# Inverter.net
KiCad netlist of a schematic drawn in Altium Designer
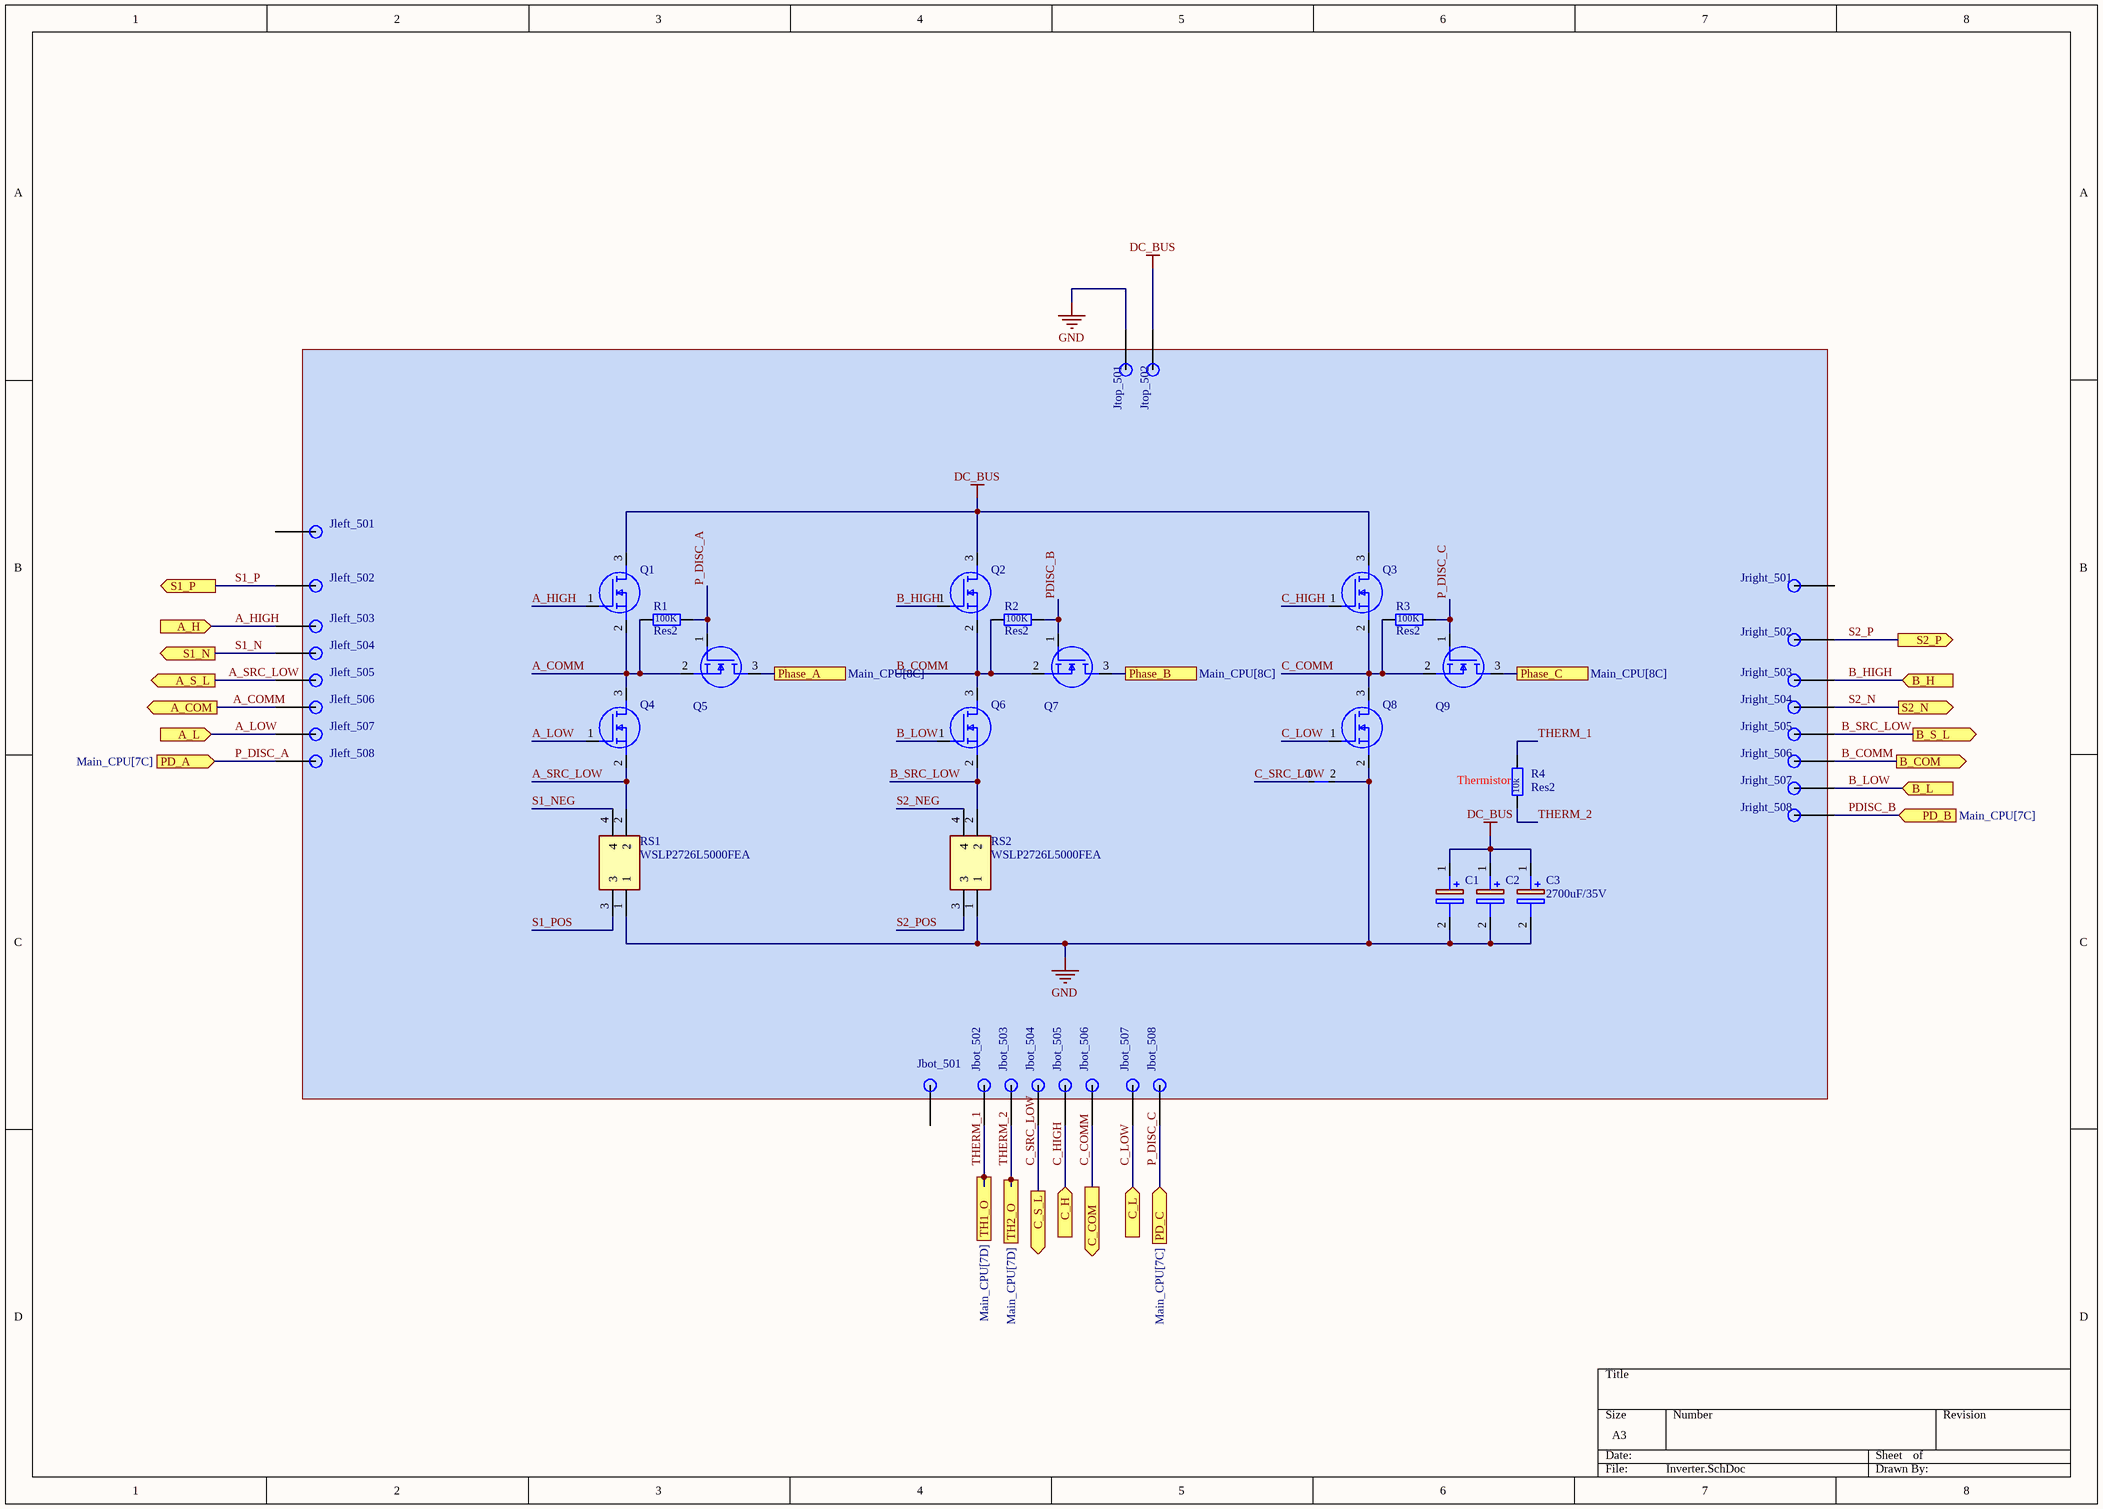
[diagram p0: Inverter.SchDoc]

(export (version "E")
  (design (tool "Eeschema 10.0.6"))
  (components
    (comp (ref "C1")
      (value "2700uF/35V")
      (footprint "SamacSys:CAPPM6032X280N")
      (description "Capacitor Polarised")
      (fields
        (field (name "MANUFACTURER_PART_NUMBER") "293D106X9025C2TE3")
        (field (name "MOUSER PART NUMBER") "74-293D106X9025C2TE3")
      )
      (libsource (lib "SamacSys") (part "293D106X9025C2TE3"))
    )
    (comp (ref "C2")
      (value "2700uF/35V")
      (footprint "SamacSys:CAPPM6032X280N")
      (description "Capacitor Polarised")
      (fields
        (field (name "MANUFACTURER_PART_NUMBER") "293D106X9025C2TE3")
        (field (name "MOUSER PART NUMBER") "74-293D106X9025C2TE3")
      )
      (libsource (lib "SamacSys") (part "293D106X9025C2TE3"))
    )
    (comp (ref "C3")
      (value "2700uF/35V")
      (footprint "SamacSys:CAPPM6032X280N")
      (description "Capacitor Polarised")
      (fields
        (field (name "MANUFACTURER_PART_NUMBER") "293D106X9025C2TE3")
        (field (name "MOUSER PART NUMBER") "74-293D106X9025C2TE3")
      )
      (libsource (lib "SamacSys") (part "293D106X9025C2TE3"))
    )
    (comp (ref "Jbot_501")
      (value "Pin_1mm")
      (footprint "Pin_1.5mm")
      (description "Pin_Connector")
      (fields (field (name "MPN") "X5511FV-02-C70D30-1000"))
      (libsource (lib "SamacSys") (part "Pin_1mm"))
    )
    (comp (ref "Jbot_502")
      (value "Pin_1mm")
      (footprint "Pin_1mm")
      (description "Pin_Connector")
      (fields (field (name "MPN") "X5511FV-02-C70D30-1000"))
      (libsource (lib "SamacSys") (part "Pin_1mm"))
    )
    (comp (ref "Jbot_503")
      (value "Pin_1mm")
      (footprint "Pin_1mm")
      (description "Pin_Connector")
      (fields (field (name "MPN") "X5511FV-02-C70D30-1000"))
      (libsource (lib "SamacSys") (part "Pin_1mm"))
    )
    (comp (ref "Jbot_504")
      (value "Pin_1mm")
      (footprint "Pin_1mm")
      (description "Pin_Connector")
      (fields (field (name "MPN") "X5511FV-02-C70D30-1000"))
      (libsource (lib "SamacSys") (part "Pin_1mm"))
    )
    (comp (ref "Jbot_505")
      (value "Pin_1mm")
      (footprint "Pin_1mm")
      (description "Pin_Connector")
      (fields (field (name "MPN") "X5511FV-02-C70D30-1000"))
      (libsource (lib "SamacSys") (part "Pin_1mm"))
    )
    (comp (ref "Jbot_506")
      (value "Pin_1mm")
      (footprint "Pin_1mm")
      (description "Pin_Connector")
      (fields (field (name "MPN") "X5511FV-02-C70D30-1000"))
      (libsource (lib "SamacSys") (part "Pin_1mm"))
    )
    (comp (ref "Jbot_507")
      (value "Pin_1mm")
      (footprint "Pin_1mm")
      (description "Pin_Connector")
      (fields (field (name "MPN") "X5511FV-02-C70D30-1000"))
      (libsource (lib "SamacSys") (part "Pin_1mm"))
    )
    (comp (ref "Jbot_508")
      (value "Pin_1mm")
      (footprint "Pin_1mm")
      (description "Pin_Connector")
      (fields (field (name "MPN") "X5511FV-02-C70D30-1000"))
      (libsource (lib "SamacSys") (part "Pin_1mm"))
    )
    (comp (ref "Jleft_501")
      (value "Pin_1mm")
      (footprint "Pin_1.5mm")
      (description "Pin_Connector")
      (fields (field (name "MPN") "X5511FV-02-C70D30-1000"))
      (libsource (lib "SamacSys") (part "Pin_1mm"))
    )
    (comp (ref "Jleft_502")
      (value "Pin_1mm")
      (footprint "Pin_1mm")
      (description "Pin_Connector")
      (fields (field (name "MPN") "X5511FV-02-C70D30-1000"))
      (libsource (lib "SamacSys") (part "Pin_1mm"))
    )
    (comp (ref "Jleft_503")
      (value "Pin_1mm")
      (footprint "Pin_1mm")
      (description "Pin_Connector")
      (fields (field (name "MPN") "X5511FV-02-C70D30-1000"))
      (libsource (lib "SamacSys") (part "Pin_1mm"))
    )
    (comp (ref "Jleft_504")
      (value "Pin_1mm")
      (footprint "Pin_1mm")
      (description "Pin_Connector")
      (fields (field (name "MPN") "X5511FV-02-C70D30-1000"))
      (libsource (lib "SamacSys") (part "Pin_1mm"))
    )
    (comp (ref "Jleft_505")
      (value "Pin_1mm")
      (footprint "Pin_1mm")
      (description "Pin_Connector")
      (fields (field (name "MPN") "X5511FV-02-C70D30-1000"))
      (libsource (lib "SamacSys") (part "Pin_1mm"))
    )
    (comp (ref "Jleft_506")
      (value "Pin_1mm")
      (footprint "Pin_1mm")
      (description "Pin_Connector")
      (fields (field (name "MPN") "X5511FV-02-C70D30-1000"))
      (libsource (lib "SamacSys") (part "Pin_1mm"))
    )
    (comp (ref "Jleft_507")
      (value "Pin_1mm")
      (footprint "Pin_1mm")
      (description "Pin_Connector")
      (fields (field (name "MPN") "X5511FV-02-C70D30-1000"))
      (libsource (lib "SamacSys") (part "Pin_1mm"))
    )
    (comp (ref "Jleft_508")
      (value "Pin_1mm")
      (footprint "Pin_1mm")
      (description "Pin_Connector")
      (fields (field (name "MPN") "X5511FV-02-C70D30-1000"))
      (libsource (lib "SamacSys") (part "Pin_1mm"))
    )
    (comp (ref "Jright_501")
      (value "Pin_1mm")
      (footprint "Pin_1.5mm")
      (description "Pin_Connector")
      (fields (field (name "MPN") "X5511FV-02-C70D30-1000"))
      (libsource (lib "SamacSys") (part "Pin_1mm"))
    )
    (comp (ref "Jright_502")
      (value "Pin_1mm")
      (footprint "Pin_1mm")
      (description "Pin_Connector")
      (fields (field (name "MPN") "X5511FV-02-C70D30-1000"))
      (libsource (lib "SamacSys") (part "Pin_1mm"))
    )
    (comp (ref "Jright_503")
      (value "Pin_1mm")
      (footprint "Pin_1mm")
      (description "Pin_Connector")
      (fields (field (name "MPN") "X5511FV-02-C70D30-1000"))
      (libsource (lib "SamacSys") (part "Pin_1mm"))
    )
    (comp (ref "Jright_504")
      (value "Pin_1mm")
      (footprint "Pin_1mm")
      (description "Pin_Connector")
      (fields (field (name "MPN") "X5511FV-02-C70D30-1000"))
      (libsource (lib "SamacSys") (part "Pin_1mm"))
    )
    (comp (ref "Jright_505")
      (value "Pin_1mm")
      (footprint "Pin_1mm")
      (description "Pin_Connector")
      (fields (field (name "MPN") "X5511FV-02-C70D30-1000"))
      (libsource (lib "SamacSys") (part "Pin_1mm"))
    )
    (comp (ref "Jright_506")
      (value "Pin_1mm")
      (footprint "Pin_1mm")
      (description "Pin_Connector")
      (fields (field (name "MPN") "X5511FV-02-C70D30-1000"))
      (libsource (lib "SamacSys") (part "Pin_1mm"))
    )
    (comp (ref "Jright_507")
      (value "Pin_1mm")
      (footprint "Pin_1mm")
      (description "Pin_Connector")
      (fields (field (name "MPN") "X5511FV-02-C70D30-1000"))
      (libsource (lib "SamacSys") (part "Pin_1mm"))
    )
    (comp (ref "Jright_508")
      (value "Pin_1mm")
      (footprint "Pin_1mm")
      (description "Pin_Connector")
      (fields (field (name "MPN") "X5511FV-02-C70D30-1000"))
      (libsource (lib "SamacSys") (part "Pin_1mm"))
    )
    (comp (ref "Jtop_501")
      (value "Pin_1mm")
      (footprint "Pin_1mm")
      (description "Pin_Connector")
      (fields (field (name "MPN") "X5511FV-02-C70D30-1000"))
      (libsource (lib "SamacSys") (part "Pin_1mm"))
    )
    (comp (ref "Jtop_502")
      (value "Pin_1mm")
      (footprint "Pin_1mm")
      (description "Pin_Connector")
      (fields (field (name "MPN") "X5511FV-02-C70D30-1000"))
      (libsource (lib "SamacSys") (part "Pin_1mm"))
    )
    (comp (ref "NT501")
      (value "Net_Tie")
      (footprint "Net_Tie_SMD")
      (description "Net Tie")
      (libsource (lib "SamacSys") (part "Net_Tie"))
    )
    (comp (ref "Q1")
      (value "IPT010N08NM5ATMA1")
      (footprint "SamacSys:IPT010N08NM5ATMA1")
      (description "MOSFET (N-Channel)")
      (fields (field (name "MOUSER PART NUMBER") "726-IPT010N08NM5ATM1"))
      (libsource (lib "SamacSys") (part "IPT010N08NM5ATMA1"))
    )
    (comp (ref "Q2")
      (value "IPT010N08NM5ATMA1")
      (footprint "SamacSys:IPT010N08NM5ATMA1")
      (description "MOSFET (N-Channel)")
      (fields (field (name "MOUSER PART NUMBER") "726-IPT010N08NM5ATM1"))
      (libsource (lib "SamacSys") (part "IPT010N08NM5ATMA1"))
    )
    (comp (ref "Q3")
      (value "IPT010N08NM5ATMA1")
      (footprint "SamacSys:IPT010N08NM5ATMA1")
      (description "MOSFET (N-Channel)")
      (fields (field (name "MOUSER PART NUMBER") "726-IPT010N08NM5ATM1"))
      (libsource (lib "SamacSys") (part "IPT010N08NM5ATMA1"))
    )
    (comp (ref "Q4")
      (value "IPT010N08NM5ATMA1")
      (footprint "SamacSys:IPT010N08NM5ATMA1")
      (description "MOSFET (N-Channel)")
      (fields (field (name "MOUSER PART NUMBER") "726-IPT010N08NM5ATM1"))
      (libsource (lib "SamacSys") (part "IPT010N08NM5ATMA1"))
    )
    (comp (ref "Q5")
      (value "IPT010N08NM5ATMA1")
      (footprint "SamacSys:IPT010N08NM5ATMA1")
      (description "MOSFET (N-Channel)")
      (fields (field (name "MOUSER PART NUMBER") "726-IPT010N08NM5ATM1"))
      (libsource (lib "SamacSys") (part "IPT010N08NM5ATMA1"))
    )
    (comp (ref "Q6")
      (value "IPT010N08NM5ATMA1")
      (footprint "SamacSys:IPT010N08NM5ATMA1")
      (description "MOSFET (N-Channel)")
      (fields (field (name "MOUSER PART NUMBER") "726-IPT010N08NM5ATM1"))
      (libsource (lib "SamacSys") (part "IPT010N08NM5ATMA1"))
    )
    (comp (ref "Q7")
      (value "IPT010N08NM5ATMA1")
      (footprint "SamacSys:IPT010N08NM5ATMA1")
      (description "MOSFET (N-Channel)")
      (fields (field (name "MOUSER PART NUMBER") "726-IPT010N08NM5ATM1"))
      (libsource (lib "SamacSys") (part "IPT010N08NM5ATMA1"))
    )
    (comp (ref "Q8")
      (value "IPT010N08NM5ATMA1")
      (footprint "SamacSys:IPT010N08NM5ATMA1")
      (description "MOSFET (N-Channel)")
      (fields (field (name "MOUSER PART NUMBER") "726-IPT010N08NM5ATM1"))
      (libsource (lib "SamacSys") (part "IPT010N08NM5ATMA1"))
    )
    (comp (ref "Q9")
      (value "IPT010N08NM5ATMA1")
      (footprint "SamacSys:IPT010N08NM5ATMA1")
      (description "MOSFET (N-Channel)")
      (fields (field (name "MOUSER PART NUMBER") "726-IPT010N08NM5ATM1"))
      (libsource (lib "SamacSys") (part "IPT010N08NM5ATMA1"))
    )
    (comp (ref "R1")
      (value "Res2")
      (footprint "AXIAL-0.4")
      (description "Resistor")
      (fields (field (name "ALTIUM_VALUE") "100K") (field (name "PUBLISHER") "Altium Limited"))
      (libsource (lib "Miscellaneous Devices") (part "Res2"))
    )
    (comp (ref "R2")
      (value "Res2")
      (footprint "AXIAL-0.4")
      (description "Resistor")
      (fields (field (name "ALTIUM_VALUE") "100K") (field (name "PUBLISHER") "Altium Limited"))
      (libsource (lib "Miscellaneous Devices") (part "Res2"))
    )
    (comp (ref "R3")
      (value "Res2")
      (footprint "AXIAL-0.4")
      (description "Resistor")
      (fields (field (name "ALTIUM_VALUE") "100K") (field (name "PUBLISHER") "Altium Limited"))
      (libsource (lib "Miscellaneous Devices") (part "Res2"))
    )
    (comp (ref "R4")
      (value "Res2")
      (footprint "AXIAL-0.4")
      (description "Resistor")
      (fields (field (name "ALTIUM_VALUE") "10k") (field (name "PUBLISHER") "Altium Limited"))
      (libsource (lib "") (part "Res2_1"))
    )
    (comp (ref "RS1")
      (value "WSLP2726L5000FEA")
      (footprint "SamacSys:WSL27261L000FEA")
      (description "Resistor")
      (fields (field (name "MOUSER PART NUMBER") "71-WSLP2726L5000FEA"))
      (libsource (lib "SamacSys") (part "WSLP2726L5000FEA"))
    )
    (comp (ref "RS2")
      (value "WSLP2726L5000FEA")
      (footprint "SamacSys:WSL27261L000FEA")
      (description "Resistor")
      (fields (field (name "MOUSER PART NUMBER") "71-WSLP2726L5000FEA"))
      (libsource (lib "SamacSys") (part "WSLP2726L5000FEA"))
    )
  )
  (nets
    (net (code "1") (name "/A_COMM") (class "Default")
      (node (ref "Jleft_506") (pin "1") (pinfunction "1_1") (pintype "passive"))
      (node (ref "Q1") (pin "2") (pinfunction "S_2") (pintype "passive"))
      (node (ref "Q4") (pin "3") (pinfunction "D_3") (pintype "passive"))
      (node (ref "Q5") (pin "2") (pinfunction "S_2") (pintype "passive"))
      (node (ref "R1") (pin "1") (pinfunction "1_1") (pintype "passive"))
    )
    (net (code "2") (name "/A_HIGH") (class "Default")
      (node (ref "Jleft_503") (pin "1") (pinfunction "1_1") (pintype "passive"))
      (node (ref "Q1") (pin "1") (pinfunction "G_1") (pintype "passive"))
    )
    (net (code "3") (name "/A_LOW") (class "Default")
      (node (ref "Jleft_507") (pin "1") (pinfunction "1_1") (pintype "passive"))
      (node (ref "Q4") (pin "1") (pinfunction "G_1") (pintype "passive"))
    )
    (net (code "4") (name "/A_SRC_LOW") (class "Default")
      (node (ref "Jleft_505") (pin "1") (pinfunction "1_1") (pintype "passive"))
      (node (ref "Q4") (pin "2") (pinfunction "S_2") (pintype "passive"))
      (node (ref "RS1") (pin "2") (pinfunction "2_2") (pintype "passive"))
    )
    (net (code "5") (name "/B_COMM") (class "Default")
      (node (ref "Jright_506") (pin "1") (pinfunction "1_1") (pintype "passive"))
      (node (ref "Q2") (pin "2") (pinfunction "S_2") (pintype "passive"))
      (node (ref "Q6") (pin "3") (pinfunction "D_3") (pintype "passive"))
      (node (ref "Q7") (pin "2") (pinfunction "S_2") (pintype "passive"))
      (node (ref "R2") (pin "1") (pinfunction "1_1") (pintype "passive"))
    )
    (net (code "6") (name "/B_HIGH") (class "Default")
      (node (ref "Jright_503") (pin "1") (pinfunction "1_1") (pintype "passive"))
      (node (ref "Q2") (pin "1") (pinfunction "G_1") (pintype "passive"))
    )
    (net (code "7") (name "/B_LOW") (class "Default")
      (node (ref "Jright_507") (pin "1") (pinfunction "1_1") (pintype "passive"))
      (node (ref "Q6") (pin "1") (pinfunction "G_1") (pintype "passive"))
    )
    (net (code "8") (name "/B_SRC_LOW") (class "Default")
      (node (ref "Jright_505") (pin "1") (pinfunction "1_1") (pintype "passive"))
      (node (ref "Q6") (pin "2") (pinfunction "S_2") (pintype "passive"))
      (node (ref "RS2") (pin "2") (pinfunction "2_2") (pintype "passive"))
    )
    (net (code "9") (name "/C_COMM") (class "Default")
      (node (ref "Jbot_506") (pin "1") (pinfunction "1_1") (pintype "passive"))
      (node (ref "Q3") (pin "2") (pinfunction "S_2") (pintype "passive"))
      (node (ref "Q8") (pin "3") (pinfunction "D_3") (pintype "passive"))
      (node (ref "Q9") (pin "2") (pinfunction "S_2") (pintype "passive"))
      (node (ref "R3") (pin "1") (pinfunction "1_1") (pintype "passive"))
    )
    (net (code "10") (name "/C_HIGH") (class "Default")
      (node (ref "Jbot_505") (pin "1") (pinfunction "1_1") (pintype "passive"))
      (node (ref "Q3") (pin "1") (pinfunction "G_1") (pintype "passive"))
    )
    (net (code "11") (name "/C_LOW") (class "Default")
      (node (ref "Jbot_507") (pin "1") (pinfunction "1_1") (pintype "passive"))
      (node (ref "Q8") (pin "1") (pinfunction "G_1") (pintype "passive"))
    )
    (net (code "12") (name "/C_SRC_LOW") (class "Default")
      (node (ref "Jbot_504") (pin "1") (pinfunction "1_1") (pintype "passive"))
      (node (ref "NT501") (pin "1") (pinfunction "9_1") (pintype "passive"))
    )
    (net (code "13") (name "/PDISC_B") (class "Default")
      (node (ref "Jright_508") (pin "1") (pinfunction "1_1") (pintype "passive"))
      (node (ref "Q7") (pin "1") (pinfunction "G_1") (pintype "passive"))
      (node (ref "R2") (pin "2") (pinfunction "2_2") (pintype "passive"))
    )
    (net (code "14") (name "/P_DISC_A") (class "Default")
      (node (ref "Jleft_508") (pin "1") (pinfunction "1_1") (pintype "passive"))
      (node (ref "Q5") (pin "1") (pinfunction "G_1") (pintype "passive"))
      (node (ref "R1") (pin "2") (pinfunction "2_2") (pintype "passive"))
    )
    (net (code "15") (name "/P_DISC_C") (class "Default")
      (node (ref "Jbot_508") (pin "1") (pinfunction "1_1") (pintype "passive"))
      (node (ref "Q9") (pin "1") (pinfunction "G_1") (pintype "passive"))
      (node (ref "R3") (pin "2") (pinfunction "2_2") (pintype "passive"))
    )
    (net (code "16") (name "/Phase_A") (class "Default")
      (node (ref "Q5") (pin "3") (pinfunction "D_3") (pintype "passive"))
    )
    (net (code "17") (name "/Phase_B") (class "Default")
      (node (ref "Q7") (pin "3") (pinfunction "D_3") (pintype "passive"))
    )
    (net (code "18") (name "/Phase_C") (class "Default")
      (node (ref "Q9") (pin "3") (pinfunction "D_3") (pintype "passive"))
    )
    (net (code "19") (name "/S1_N") (class "Default")
      (node (ref "Jleft_504") (pin "1") (pinfunction "1_1") (pintype "passive"))
    )
    (net (code "20") (name "/S1_NEG") (class "Default")
      (node (ref "RS1") (pin "4") (pinfunction "4_4") (pintype "passive"))
    )
    (net (code "21") (name "/S1_P") (class "Default")
      (node (ref "Jleft_502") (pin "1") (pinfunction "1_1") (pintype "passive"))
    )
    (net (code "22") (name "/S1_POS") (class "Default")
      (node (ref "RS1") (pin "3") (pinfunction "3_3") (pintype "passive"))
    )
    (net (code "23") (name "/S2_N") (class "Default")
      (node (ref "Jright_504") (pin "1") (pinfunction "1_1") (pintype "passive"))
    )
    (net (code "24") (name "/S2_NEG") (class "Default")
      (node (ref "RS2") (pin "4") (pinfunction "4_4") (pintype "passive"))
    )
    (net (code "25") (name "/S2_P") (class "Default")
      (node (ref "Jright_502") (pin "1") (pinfunction "1_1") (pintype "passive"))
    )
    (net (code "26") (name "/S2_POS") (class "Default")
      (node (ref "RS2") (pin "3") (pinfunction "3_3") (pintype "passive"))
    )
    (net (code "27") (name "/THERM_1") (class "Default")
      (node (ref "Jbot_502") (pin "1") (pinfunction "1_1") (pintype "passive"))
      (node (ref "R4") (pin "2") (pinfunction "2_2") (pintype "passive"))
    )
    (net (code "28") (name "/THERM_2") (class "Default")
      (node (ref "Jbot_503") (pin "1") (pinfunction "1_1") (pintype "passive"))
      (node (ref "R4") (pin "1") (pinfunction "1_1") (pintype "passive"))
    )
    (net (code "29") (name "DC_BUS") (class "Default")
      (node (ref "C1") (pin "1") (pinfunction "+_1") (pintype "passive"))
      (node (ref "C2") (pin "1") (pinfunction "+_1") (pintype "passive"))
      (node (ref "C3") (pin "1") (pinfunction "+_1") (pintype "passive"))
      (node (ref "Jtop_502") (pin "1") (pinfunction "1_1") (pintype "passive"))
      (node (ref "Q1") (pin "3") (pinfunction "D_3") (pintype "passive"))
      (node (ref "Q2") (pin "3") (pinfunction "D_3") (pintype "passive"))
      (node (ref "Q3") (pin "3") (pinfunction "D_3") (pintype "passive"))
    )
    (net (code "30") (name "GND") (class "Default")
      (node (ref "C1") (pin "2") (pinfunction "-_2") (pintype "passive"))
      (node (ref "C2") (pin "2") (pinfunction "-_2") (pintype "passive"))
      (node (ref "C3") (pin "2") (pinfunction "-_2") (pintype "passive"))
      (node (ref "Jtop_501") (pin "1") (pinfunction "1_1") (pintype "passive"))
      (node (ref "NT501") (pin "2") (pinfunction "10_2") (pintype "passive"))
      (node (ref "Q8") (pin "2") (pinfunction "S_2") (pintype "passive"))
      (node (ref "RS1") (pin "1") (pinfunction "1_1") (pintype "passive"))
      (node (ref "RS2") (pin "1") (pinfunction "1_1") (pintype "passive"))
    )
    (net (code "31") (name "unconnected-(Jbot_501-Pad1)") (class "Default")
      (node (ref "Jbot_501") (pin "1") (pinfunction "1_1") (pintype "passive"))
    )
    (net (code "32") (name "unconnected-(Jleft_501-Pad1)") (class "Default")
      (node (ref "Jleft_501") (pin "1") (pinfunction "1_1") (pintype "passive"))
    )
    (net (code "33") (name "unconnected-(Jright_501-Pad1)") (class "Default")
      (node (ref "Jright_501") (pin "1") (pinfunction "1_1") (pintype "passive"))
    )
  )
)
